# RTI-Dome-eth.net
KiCad netlist of a schematic drawn in EAGLE
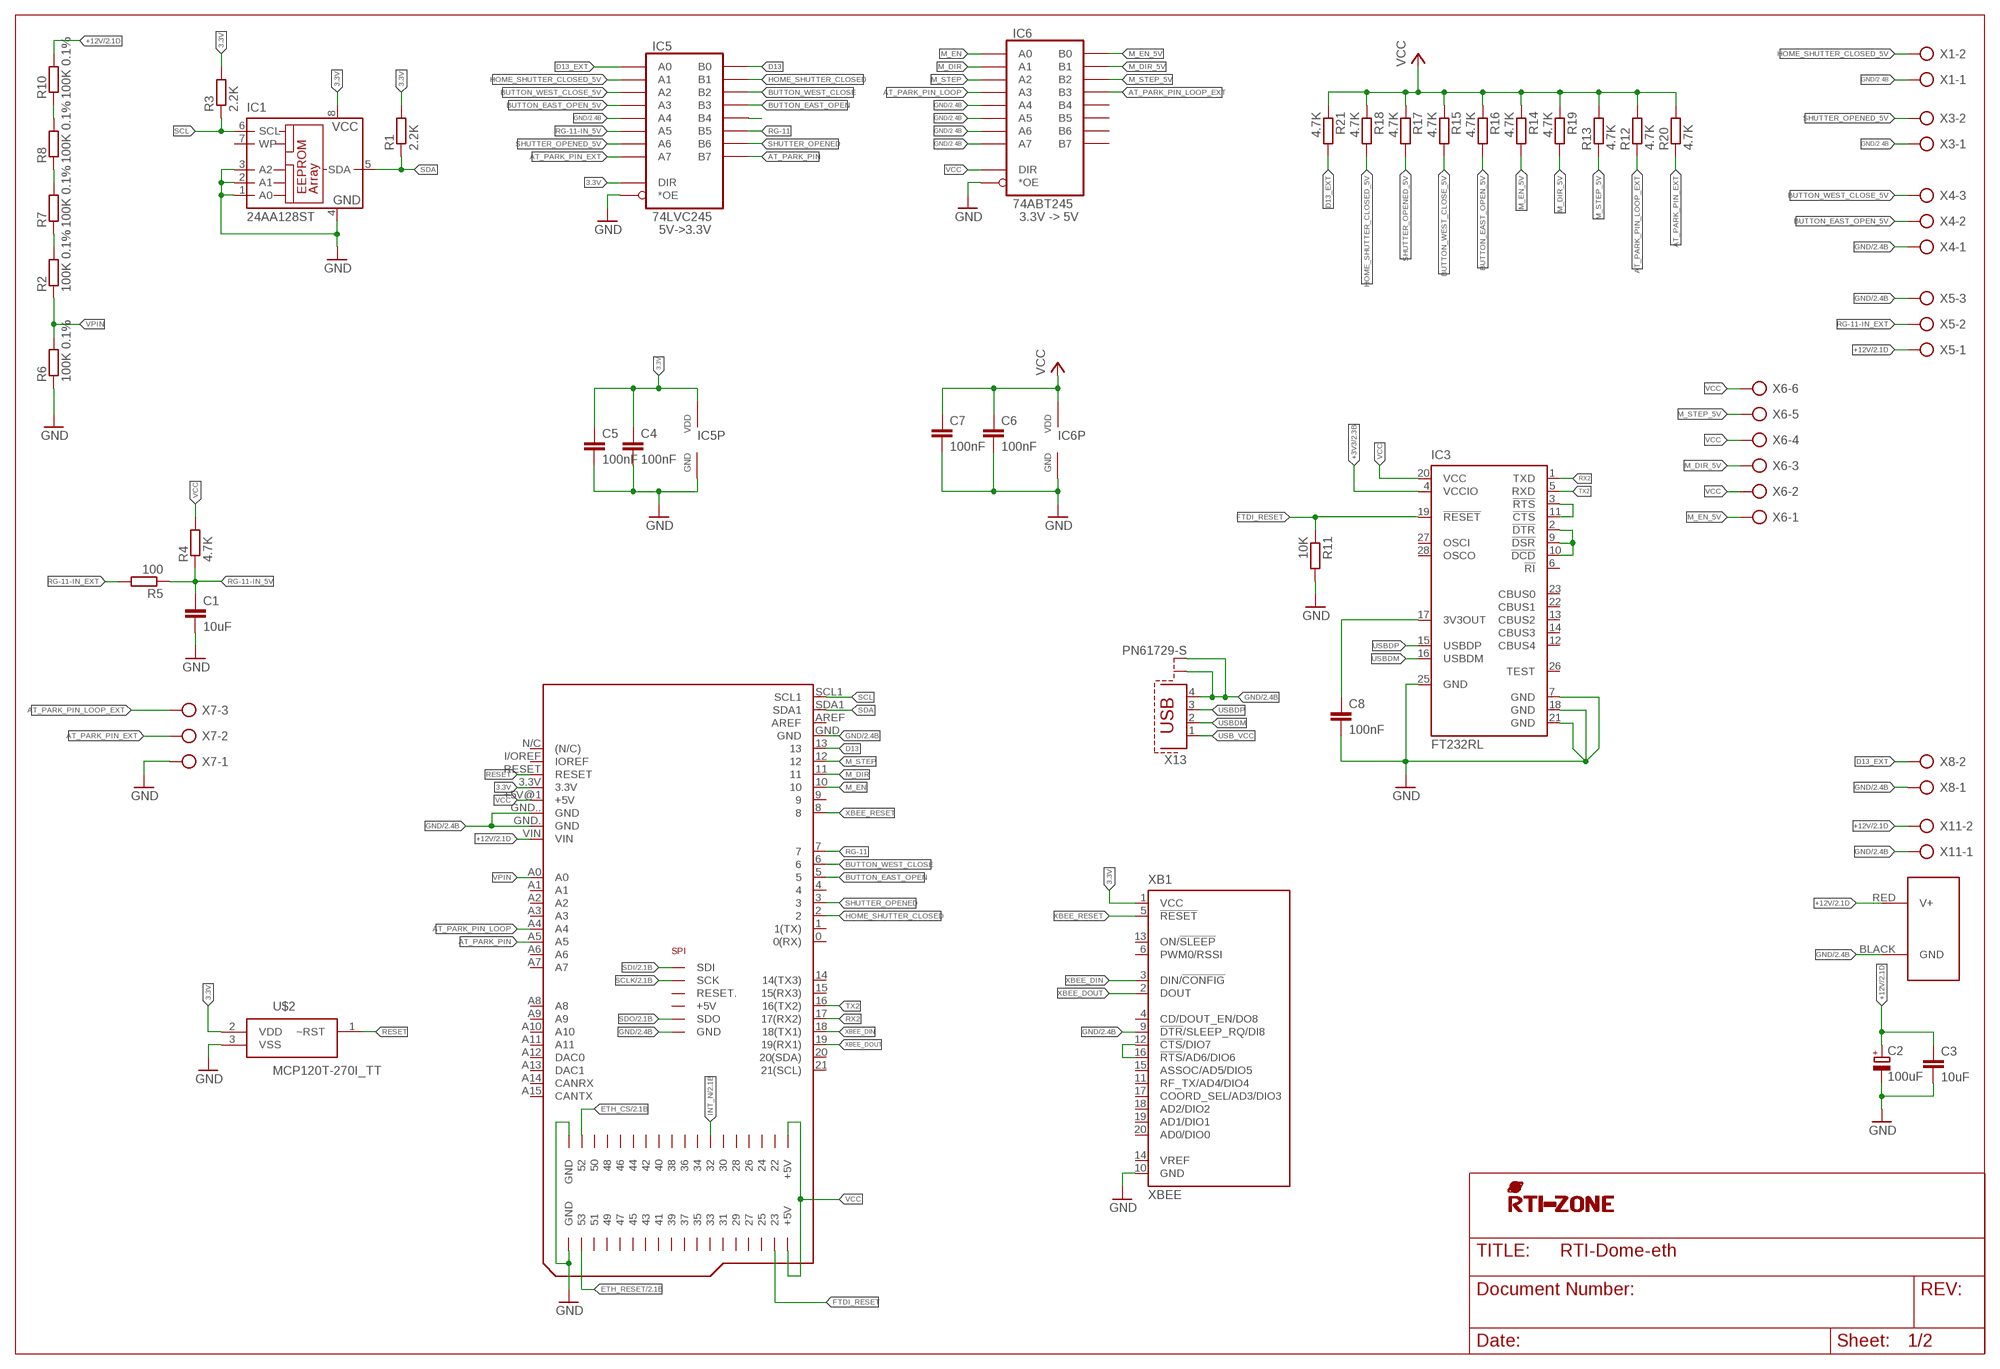
[diagram p0: schematic, sheet 1]
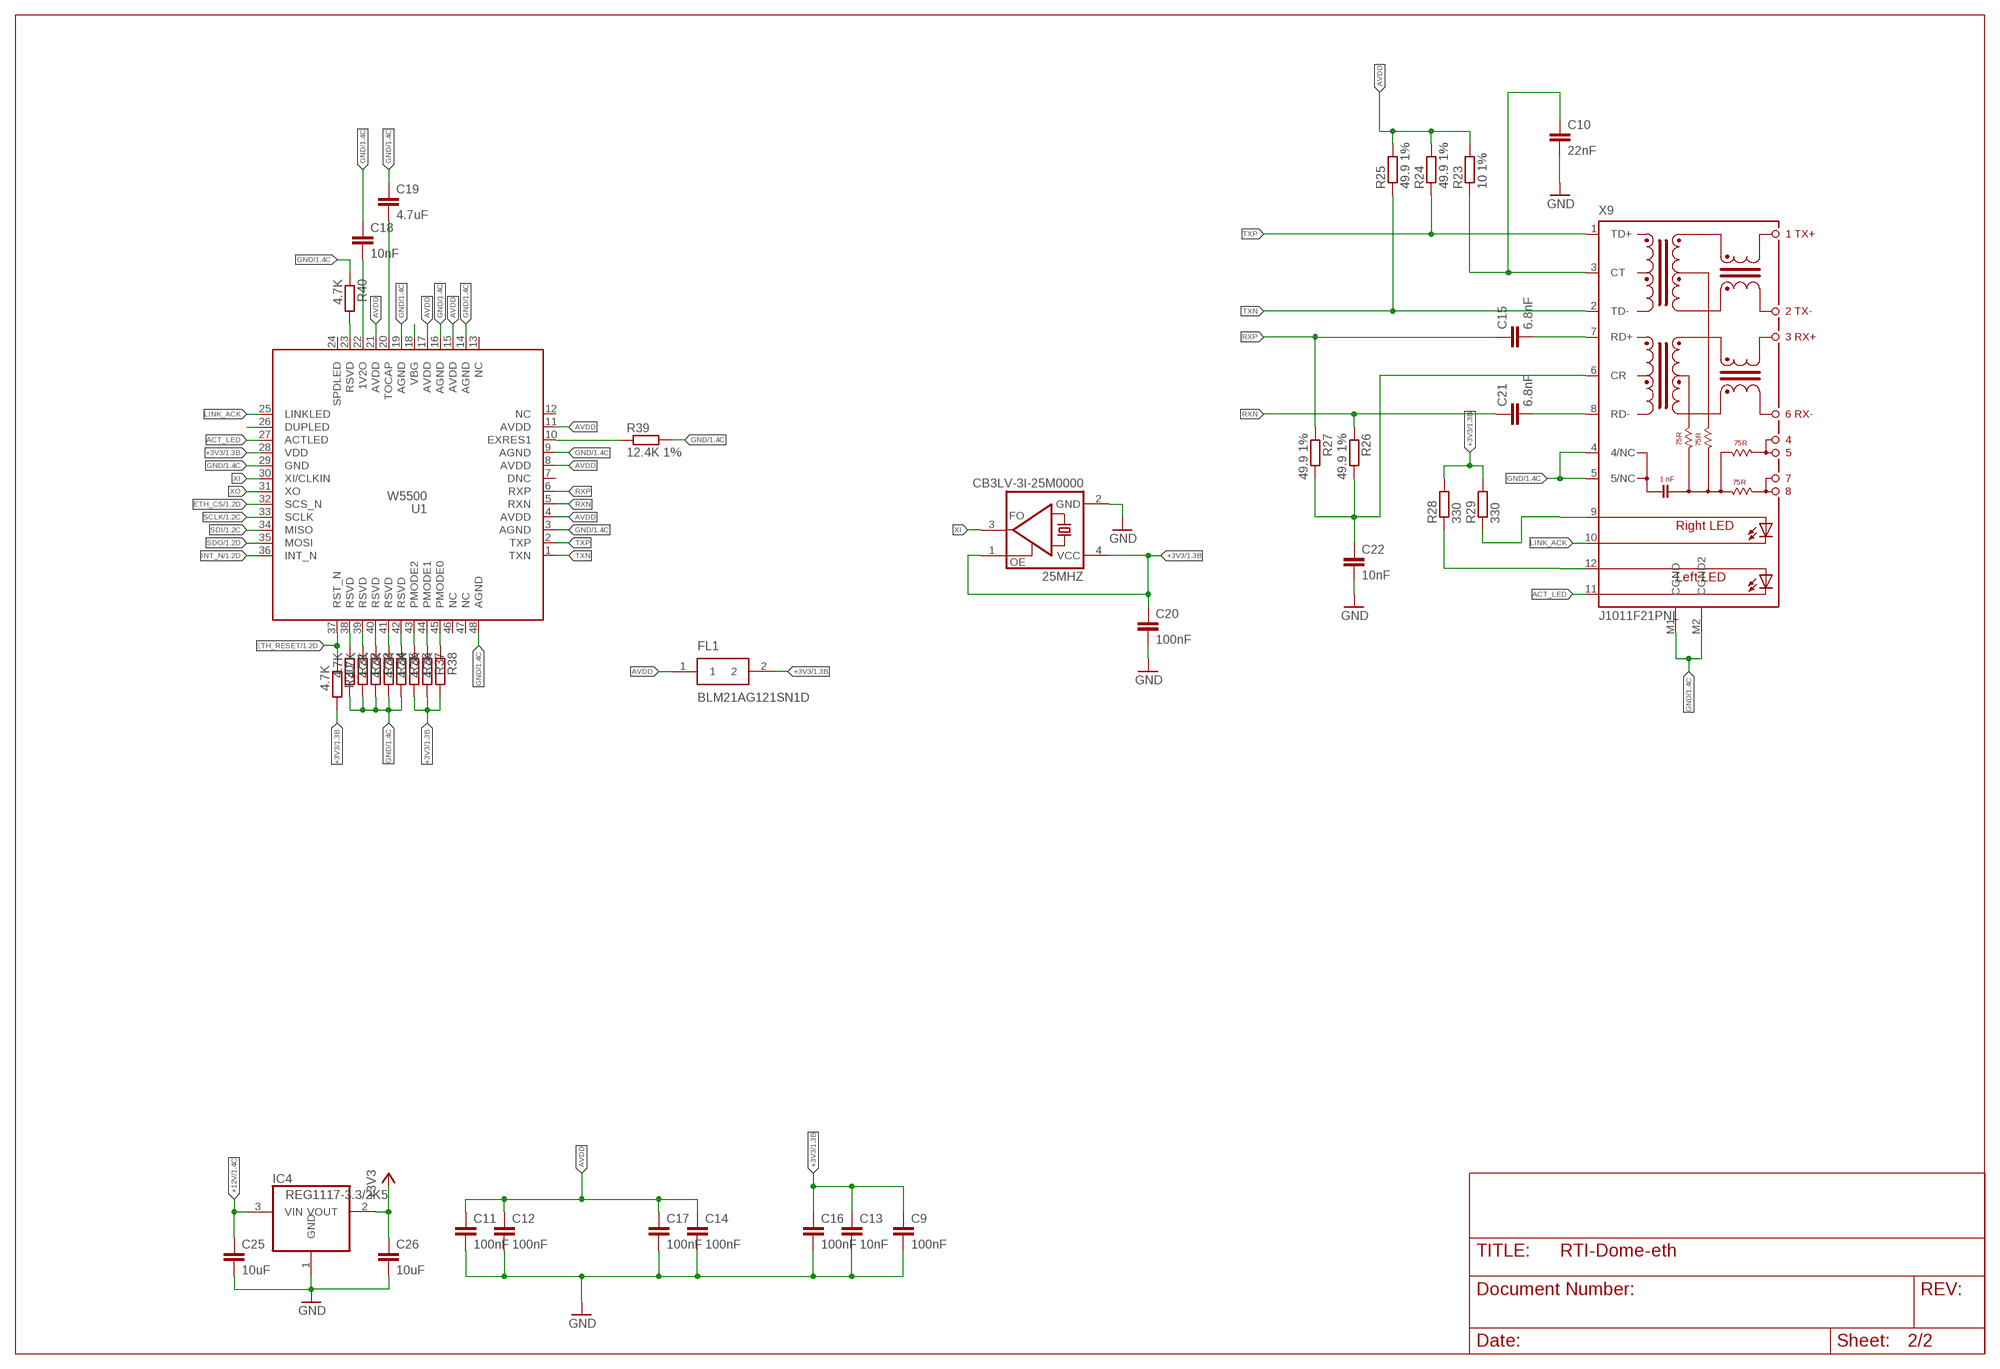
[diagram p1: schematic, sheet 2]

(export (version "E")
  (design (tool "Eeschema 10.0.6"))
  (components
    (comp (ref "C1")
      (value "10uF")
      (footprint "eagle-import:C0805")
      (fields (field (name "MPN") "CC0805KKX5R8BB106"))
      (libsource (lib "eagle-import") (part "C-EU'0805'"))
    )
    (comp (ref "C2")
      (value "100uF")
      (footprint "eagle-import:UD-10X10_NICHICON")
      (fields (field (name "MPN") "MAL215099804E3"))
      (libsource (lib "eagle-import") (part "CPOL-EU"))
    )
    (comp (ref "C3")
      (value "10uF")
      (footprint "eagle-import:C0805")
      (fields (field (name "MPN") "CC0805KKX5R8BB106"))
      (libsource (lib "eagle-import") (part "C-EU'0805'"))
    )
    (comp (ref "C4")
      (value "100nF")
      (footprint "eagle-import:C0805")
      (fields (field (name "MPN") "0805YD104KAT2A"))
      (libsource (lib "eagle-import") (part "C-EU'0805'"))
    )
    (comp (ref "C5")
      (value "100nF")
      (footprint "eagle-import:C0805")
      (fields (field (name "MPN") "0805YD104KAT2A"))
      (libsource (lib "eagle-import") (part "C-EU'0805'"))
    )
    (comp (ref "C6")
      (value "100nF")
      (footprint "eagle-import:C0805")
      (fields (field (name "MPN") "0805YD104KAT2A"))
      (libsource (lib "eagle-import") (part "C-EU'0805'"))
    )
    (comp (ref "C7")
      (value "100nF")
      (footprint "eagle-import:C0805")
      (fields (field (name "MPN") "0805YD104KAT2A"))
      (libsource (lib "eagle-import") (part "C-EU'0805'"))
    )
    (comp (ref "C8")
      (value "100nF")
      (footprint "eagle-import:C0805")
      (fields (field (name "MPN") "0805YD104KAT2A"))
      (libsource (lib "eagle-import") (part "C-EU'0805'"))
    )
    (comp (ref "IC1")
      (value "24AA128ST")
      (footprint "eagle-import:TSSOP8")
      (fields (field (name "MF") "MICROCHIP") (field (name "MPN") "24AA128-I/ST"))
      (libsource (lib "eagle-import") (part "24STAA128"))
    )
    (comp (ref "IC3")
      (value "FT232RL")
      (footprint "eagle-import:SSOP28")
      (fields (field (name "MPN") "FT232RL-REEL"))
      (libsource (lib "eagle-import") (part "FT232RL"))
    )
    (comp (ref "IC5")
      (value "74LVC245")
      (footprint "eagle-import:TSSOP20")
      (fields (field (name "MPN") "74LVC245APW,112"))
      (libsource (lib "eagle-import") (part "74245LVC"))
    )
    (comp (ref "IC6")
      (value "74ABT245")
      (footprint "eagle-import:TSSOP20")
      (fields (field (name "MPN") "74ABT245PW,112"))
      (libsource (lib "eagle-import") (part "74245ABT"))
    )
    (comp (ref "J1")
      (value "POWERPOLE_POWER45A")
      (footprint "eagle-import:POWERPOLE_PAIR_45A")
      (libsource (lib "eagle-import") (part "POWERPOLE_POWER45A"))
    )
    (comp (ref "R1")
      (value "2.2K")
      (footprint "eagle-import:R0805")
      (fields (field (name "MPN") "RT0805FRE071KL"))
      (libsource (lib "eagle-import") (part "R-EU'0805'"))
    )
    (comp (ref "R2")
      (value "100K 0.1%")
      (footprint "eagle-import:R0805")
      (fields (field (name "MPN") "AT0805BRD07100KL"))
      (libsource (lib "eagle-import") (part "R-EU'0805'"))
    )
    (comp (ref "R3")
      (value "2.2K")
      (footprint "eagle-import:R0805")
      (fields (field (name "MPN") "RT0805FRE071KL"))
      (libsource (lib "eagle-import") (part "R-EU'0805'"))
    )
    (comp (ref "R4")
      (value "4.7K")
      (footprint "eagle-import:R0805")
      (fields (field (name "MPN") "RT0805FRE074K7L"))
      (libsource (lib "eagle-import") (part "R-EU'0805'"))
    )
    (comp (ref "R5")
      (value "100")
      (footprint "eagle-import:R0805")
      (fields (field (name "MPN") "RT0805FRD07100RL"))
      (libsource (lib "eagle-import") (part "R-EU'0805'"))
    )
    (comp (ref "R6")
      (value "100K 0.1%")
      (footprint "eagle-import:R0805")
      (fields (field (name "MPN") "AT0805BRD07100KL"))
      (libsource (lib "eagle-import") (part "R-EU'0805'"))
    )
    (comp (ref "R7")
      (value "100K 0.1%")
      (footprint "eagle-import:R0805")
      (fields (field (name "MPN") "AT0805BRD07100KL"))
      (libsource (lib "eagle-import") (part "R-EU'0805'"))
    )
    (comp (ref "R8")
      (value "100K 0.1%")
      (footprint "eagle-import:R0805")
      (fields (field (name "MPN") "AT0805BRD07100KL"))
      (libsource (lib "eagle-import") (part "R-EU'0805'"))
    )
    (comp (ref "R10")
      (value "100K 0.1%")
      (footprint "eagle-import:R0805")
      (fields (field (name "MPN") "AT0805BRD07100KL"))
      (libsource (lib "eagle-import") (part "R-EU'0805'"))
    )
    (comp (ref "R11")
      (value "10K")
      (footprint "eagle-import:R0805")
      (fields (field (name "MPN") "RT0805FRE0710KL"))
      (libsource (lib "eagle-import") (part "R-EU'0805'"))
    )
    (comp (ref "R12")
      (value "4.7K")
      (footprint "eagle-import:R0805")
      (fields (field (name "MPN") "RT0805FRE074K7L"))
      (libsource (lib "eagle-import") (part "R-EU'0805'"))
    )
    (comp (ref "R13")
      (value "4.7K")
      (footprint "eagle-import:R0805")
      (fields (field (name "MPN") "RT0805FRE074K7L"))
      (libsource (lib "eagle-import") (part "R-EU'0805'"))
    )
    (comp (ref "R14")
      (value "4.7K")
      (footprint "eagle-import:R0805")
      (fields (field (name "MPN") "RT0805FRE074K7L"))
      (libsource (lib "eagle-import") (part "R-EU'0805'"))
    )
    (comp (ref "R15")
      (value "4.7K")
      (footprint "eagle-import:R0805")
      (fields (field (name "MPN") "RT0805FRE074K7L"))
      (libsource (lib "eagle-import") (part "R-EU'0805'"))
    )
    (comp (ref "R16")
      (value "4.7K")
      (footprint "eagle-import:R0805")
      (fields (field (name "MPN") "RT0805FRE074K7L"))
      (libsource (lib "eagle-import") (part "R-EU'0805'"))
    )
    (comp (ref "R17")
      (value "4.7K")
      (footprint "eagle-import:R0805")
      (fields (field (name "MPN") "RT0805FRE074K7L"))
      (libsource (lib "eagle-import") (part "R-EU'0805'"))
    )
    (comp (ref "R18")
      (value "4.7K")
      (footprint "eagle-import:R0805")
      (fields (field (name "MPN") "RT0805FRE074K7L"))
      (libsource (lib "eagle-import") (part "R-EU'0805'"))
    )
    (comp (ref "R19")
      (value "4.7K")
      (footprint "eagle-import:R0805")
      (fields (field (name "MPN") "RT0805FRE074K7L"))
      (libsource (lib "eagle-import") (part "R-EU'0805'"))
    )
    (comp (ref "R20")
      (value "4.7K")
      (footprint "eagle-import:R0805")
      (fields (field (name "MPN") "RT0805FRE074K7L"))
      (libsource (lib "eagle-import") (part "R-EU'0805'"))
    )
    (comp (ref "R21")
      (value "4.7K")
      (footprint "eagle-import:R0805")
      (fields (field (name "MPN") "RT0805FRE074K7L"))
      (libsource (lib "eagle-import") (part "R-EU'0805'"))
    )
    (comp (ref "U$1")
      (value "ARDUINO_DUE_SHIELD_FULL")
      (footprint "eagle-import:ARDUINO_DUE_SHIELD_FULL")
      (libsource (lib "eagle-import") (part "ARDUINO_DUE_SHIELD_FULL"))
    )
    (comp (ref "U$2")
      (value "MCP120T-270I_TT")
      (footprint "eagle-import:SOT95P237X112-3N")
      (fields
        (field (name "MANUFACTURER_PART_NUMBER") "MCP120T-270I/TT")
        (field (name "MOUSER_PART_NUMBER") "579-MCP120T-270I/TT")
      )
      (libsource (lib "eagle-import") (part "MCP120T-270I_TT"))
    )
    (comp (ref "U$4")
      (value "RTI-LOGO_BIG")
      (footprint "eagle-import:LOGO_BIG")
      (libsource (lib "eagle-import") (part "RTI-LOGO_BIG"))
    )
    (comp (ref "X1")
      (value "AK500/2")
      (footprint "eagle-import:AK500_2")
      (fields (field (name "MPN") "691101710002"))
      (libsource (lib "eagle-import") (part "AK500/2"))
    )
    (comp (ref "X3")
      (value "AK500/2")
      (footprint "eagle-import:AK500_2")
      (fields (field (name "MPN") "691101710002"))
      (libsource (lib "eagle-import") (part "AK500/2"))
    )
    (comp (ref "X4")
      (value "AK500/3")
      (footprint "eagle-import:AK500_3")
      (fields (field (name "MPN") "691101710003"))
      (libsource (lib "eagle-import") (part "AK500/3"))
    )
    (comp (ref "X5")
      (value "AK500/3")
      (footprint "eagle-import:AK500_3")
      (fields (field (name "MPN") "691101710003"))
      (libsource (lib "eagle-import") (part "AK500/3"))
    )
    (comp (ref "X6")
      (value "AK500/6")
      (footprint "eagle-import:AK500_6")
      (fields (field (name "MPN") "30.706"))
      (libsource (lib "eagle-import") (part "AK500/6"))
    )
    (comp (ref "X7")
      (value "AK500/3")
      (footprint "eagle-import:AK500_3")
      (fields (field (name "MPN") "691101710003"))
      (libsource (lib "eagle-import") (part "AK500/3"))
    )
    (comp (ref "X8")
      (value "AK500/2")
      (footprint "eagle-import:AK500_2")
      (fields (field (name "MPN") "691101710002"))
      (libsource (lib "eagle-import") (part "AK500/2"))
    )
    (comp (ref "X11")
      (value "AK500/2")
      (footprint "eagle-import:AK500_2")
      (fields (field (name "MPN") "691101710002"))
      (libsource (lib "eagle-import") (part "AK500/2"))
    )
    (comp (ref "X13")
      (value "PN61729-S")
      (footprint "eagle-import:PN61729-S")
      (fields (field (name "MPN") "SS-52300-001"))
      (libsource (lib "eagle-import") (part "PN61729-S"))
    )
    (comp (ref "XB1")
      (value "XBEE")
      (footprint "eagle-import:XBEE")
      (fields (field (name "MPN") "XBP24-Z7UIT-004"))
      (libsource (lib "eagle-import") (part "XBEE"))
    )
    (comp (ref "25MHZ")
      (value "CB3LV-3I-25M0000")
      (footprint "eagle-import:SMD-7050_4P")
      (libsource (lib "eagle-import") (part "CB3LV-OSCILATOR"))
    )
    (comp (ref "C9")
      (value "100nF")
      (footprint "eagle-import:C0805")
      (fields (field (name "MPN") "0805YD104KAT2A"))
      (libsource (lib "eagle-import") (part "C-EU'0805'"))
    )
    (comp (ref "C10")
      (value "22nF")
      (footprint "eagle-import:C0805")
      (fields (field (name "MPN") "CC0805JRX7R8BB223"))
      (libsource (lib "eagle-import") (part "C-EU'0805'"))
    )
    (comp (ref "C11")
      (value "100nF")
      (footprint "eagle-import:C0805")
      (fields (field (name "MPN") "0805YD104KAT2A"))
      (libsource (lib "eagle-import") (part "C-EU'0805'"))
    )
    (comp (ref "C12")
      (value "100nF")
      (footprint "eagle-import:C0805")
      (fields (field (name "MPN") "0805YD104KAT2A"))
      (libsource (lib "eagle-import") (part "C-EU'0805'"))
    )
    (comp (ref "C13")
      (value "10nF")
      (footprint "eagle-import:C0805")
      (fields (field (name "MPN") " CC0805KRX7R9BB103"))
      (libsource (lib "eagle-import") (part "C-EU'0805'"))
    )
    (comp (ref "C14")
      (value "100nF")
      (footprint "eagle-import:C0805")
      (fields (field (name "MPN") "0805YD104KAT2A"))
      (libsource (lib "eagle-import") (part "C-EU'0805'"))
    )
    (comp (ref "C15")
      (value "6.8nF")
      (footprint "eagle-import:C0805")
      (fields (field (name "MPN") "C0805C682F4HACTU"))
      (libsource (lib "eagle-import") (part "C-EU'0805'"))
    )
    (comp (ref "C16")
      (value "100nF")
      (footprint "eagle-import:C0805")
      (fields (field (name "MPN") "0805YD104KAT2A"))
      (libsource (lib "eagle-import") (part "C-EU'0805'"))
    )
    (comp (ref "C17")
      (value "100nF")
      (footprint "eagle-import:C0805")
      (fields (field (name "MPN") "0805YD104KAT2A"))
      (libsource (lib "eagle-import") (part "C-EU'0805'"))
    )
    (comp (ref "C18")
      (value "10nF")
      (footprint "eagle-import:C0805")
      (fields (field (name "MPN") " CC0805KRX7R9BB103"))
      (libsource (lib "eagle-import") (part "C-EU'0805'"))
    )
    (comp (ref "C19")
      (value "4.7uF")
      (footprint "eagle-import:C0805")
      (fields (field (name "MPN") "C0805C475J3RACTU"))
      (libsource (lib "eagle-import") (part "C-EU'0805'"))
    )
    (comp (ref "C20")
      (value "100nF")
      (footprint "eagle-import:C0805")
      (fields (field (name "MPN") "0805YD104KAT2A"))
      (libsource (lib "eagle-import") (part "C-EU'0805'"))
    )
    (comp (ref "C21")
      (value "6.8nF")
      (footprint "eagle-import:C0805")
      (fields (field (name "MPN") "C0805C682F4HACTU"))
      (libsource (lib "eagle-import") (part "C-EU'0805'"))
    )
    (comp (ref "C22")
      (value "10nF")
      (footprint "eagle-import:C0805")
      (fields (field (name "MPN") " CC0805KRX7R9BB103"))
      (libsource (lib "eagle-import") (part "C-EU'0805'"))
    )
    (comp (ref "C25")
      (value "10uF")
      (footprint "eagle-import:C0805")
      (fields (field (name "MPN") "CC0805KKX5R8BB106"))
      (libsource (lib "eagle-import") (part "C-EU'0805'"))
    )
    (comp (ref "C26")
      (value "10uF")
      (footprint "eagle-import:C0805")
      (fields (field (name "MPN") "CC0805KKX5R8BB106"))
      (libsource (lib "eagle-import") (part "C-EU'0805'"))
    )
    (comp (ref "FL1")
      (value "BLM21AG121SN1D")
      (footprint "eagle-import:L0805")
      (libsource (lib "eagle-import") (part "BLM21AG121SN1D"))
    )
    (comp (ref "IC4")
      (value "REG1117-3.3/2K5")
      (footprint "eagle-import:SOT223")
      (fields (field (name "MPN") "REG1117") (field (name "MPN_1") "REG1117-3.3/2K5"))
      (libsource (lib "eagle-import") (part "REG1117"))
    )
    (comp (ref "R23")
      (value "10 1%")
      (footprint "eagle-import:R0805")
      (fields (field (name "MPN") "RT0805FRE1310RL"))
      (libsource (lib "eagle-import") (part "R-EU'0805'"))
    )
    (comp (ref "R24")
      (value "49.9 1%")
      (footprint "eagle-import:R0805")
      (fields (field (name "MPN") "RC0805FR-0749R9L"))
      (libsource (lib "eagle-import") (part "R-EU'0805'"))
    )
    (comp (ref "R25")
      (value "49.9 1%")
      (footprint "eagle-import:R0805")
      (fields (field (name "MPN") "RC0805FR-0749R9L"))
      (libsource (lib "eagle-import") (part "R-EU'0805'"))
    )
    (comp (ref "R26")
      (value "49.9 1%")
      (footprint "eagle-import:R0805")
      (fields (field (name "MPN") "RC0805FR-0749R9L"))
      (libsource (lib "eagle-import") (part "R-EU'0805'"))
    )
    (comp (ref "R27")
      (value "49.9 1%")
      (footprint "eagle-import:R0805")
      (fields (field (name "MPN") "RC0805FR-0749R9L"))
      (libsource (lib "eagle-import") (part "R-EU'0805'"))
    )
    (comp (ref "R28")
      (value "330")
      (footprint "eagle-import:R0805")
      (fields (field (name "MPN") " RC0805JR-07330RL"))
      (libsource (lib "eagle-import") (part "R-EU'0805'"))
    )
    (comp (ref "R29")
      (value "330")
      (footprint "eagle-import:R0805")
      (fields (field (name "MPN") " RC0805JR-07330RL"))
      (libsource (lib "eagle-import") (part "R-EU'0805'"))
    )
    (comp (ref "R30")
      (value "4.7K")
      (footprint "eagle-import:R0805")
      (fields (field (name "MPN") "RT0805FRE074K7L"))
      (libsource (lib "eagle-import") (part "R-EU'0805'"))
    )
    (comp (ref "R31")
      (value "4.7K")
      (footprint "eagle-import:R0805")
      (fields (field (name "MPN") "RT0805FRE074K7L"))
      (libsource (lib "eagle-import") (part "R-EU'0805'"))
    )
    (comp (ref "R32")
      (value "4.7K")
      (footprint "eagle-import:R0805")
      (fields (field (name "MPN") "RT0805FRE074K7L"))
      (libsource (lib "eagle-import") (part "R-EU'0805'"))
    )
    (comp (ref "R33")
      (value "4.7K")
      (footprint "eagle-import:R0805")
      (fields (field (name "MPN") "RT0805FRE074K7L"))
      (libsource (lib "eagle-import") (part "R-EU'0805'"))
    )
    (comp (ref "R34")
      (value "4.7K")
      (footprint "eagle-import:R0805")
      (fields (field (name "MPN") "RT0805FRE074K7L"))
      (libsource (lib "eagle-import") (part "R-EU'0805'"))
    )
    (comp (ref "R35")
      (value "4.7K")
      (footprint "eagle-import:R0805")
      (fields (field (name "MPN") "RT0805FRE074K7L"))
      (libsource (lib "eagle-import") (part "R-EU'0805'"))
    )
    (comp (ref "R36")
      (value "4.7K")
      (footprint "eagle-import:R0805")
      (fields (field (name "MPN") "RT0805FRE074K7L"))
      (libsource (lib "eagle-import") (part "R-EU'0805'"))
    )
    (comp (ref "R37")
      (value "4.7K")
      (footprint "eagle-import:R0805")
      (fields (field (name "MPN") "RT0805FRE074K7L"))
      (libsource (lib "eagle-import") (part "R-EU'0805'"))
    )
    (comp (ref "R38")
      (value "4.7K")
      (footprint "eagle-import:R0805")
      (fields (field (name "MPN") "RT0805FRE074K7L"))
      (libsource (lib "eagle-import") (part "R-EU'0805'"))
    )
    (comp (ref "R39")
      (value "12.4K 1%")
      (footprint "eagle-import:R0805")
      (fields (field (name "MPN") "RC0805FR-0712K4L"))
      (libsource (lib "eagle-import") (part "R-EU'0805'"))
    )
    (comp (ref "R40")
      (value "4.7K")
      (footprint "eagle-import:R0805")
      (fields (field (name "MPN") "RT0805FRE074K7L"))
      (libsource (lib "eagle-import") (part "R-EU'0805'"))
    )
    (comp (ref "U1")
      (value "W5500")
      (footprint "eagle-import:LQFP48")
      (libsource (lib "eagle-import") (part "W5500"))
    )
    (comp (ref "X9")
      (value "J1011F21PNL")
      (footprint "eagle-import:J1011F21PNL")
      (fields (field (name "MPN") "J1011F21PNL"))
      (libsource (lib "eagle-import") (part "J1011F21PNL"))
    )
  )
  (nets
    (net (code "1") (name "+3V3") (class "Default")
      (node (ref "25MHZ") (pin "1") (pinfunction "OE_1") (pintype "input"))
      (node (ref "25MHZ") (pin "4") (pinfunction "VDD_4") (pintype "power_in"))
      (node (ref "C13") (pin "1") (pinfunction "1_1") (pintype "passive"))
      (node (ref "C16") (pin "1") (pinfunction "1_1") (pintype "passive"))
      (node (ref "C20") (pin "1") (pinfunction "1_1") (pintype "passive"))
      (node (ref "C26") (pin "1") (pinfunction "1_1") (pintype "passive"))
      (node (ref "C9") (pin "1") (pinfunction "1_1") (pintype "passive"))
      (node (ref "FL1") (pin "2") (pinfunction "2_2") (pintype "bidirectional"))
      (node (ref "IC3") (pin "4") (pinfunction "VCCIO_4") (pintype "power_in"))
      (node (ref "IC4") (pin "2") (pinfunction "VOUT_2") (pintype "output"))
      (node (ref "R28") (pin "2") (pinfunction "2_2") (pintype "passive"))
      (node (ref "R29") (pin "2") (pinfunction "2_2") (pintype "passive"))
      (node (ref "R30") (pin "2") (pinfunction "2_2") (pintype "passive"))
      (node (ref "R36") (pin "2") (pinfunction "2_2") (pintype "passive"))
      (node (ref "R37") (pin "2") (pinfunction "2_2") (pintype "passive"))
      (node (ref "R38") (pin "2") (pinfunction "2_2") (pintype "passive"))
      (node (ref "U1") (pin "28") (pinfunction "VDD_28") (pintype "passive"))
    )
    (net (code "2") (name "+5V") (class "Default")
      (node (ref "U$1") (pin "+5V@2") (pinfunction "+5V_+5V@2") (pintype "power_in"))
    )
    (net (code "3") (name "+12V") (class "Default")
      (node (ref "C2") (pin "+") (pinfunction "+_+") (pintype "passive"))
      (node (ref "C25") (pin "1") (pinfunction "1_1") (pintype "passive"))
      (node (ref "C3") (pin "1") (pinfunction "1_1") (pintype "passive"))
      (node (ref "IC4") (pin "3") (pinfunction "VIN_3") (pintype "input"))
      (node (ref "J1") (pin "RED") (pinfunction "V+_RED") (pintype "power_in"))
      (node (ref "R10") (pin "2") (pinfunction "2_2") (pintype "passive"))
      (node (ref "U$1") (pin "VIN") (pinfunction "VIN_VIN") (pintype "power_in"))
      (node (ref "X11") (pin "2") (pinfunction "KL_2") (pintype "passive"))
      (node (ref "X5") (pin "1") (pinfunction "KL_1") (pintype "passive"))
    )
    (net (code "4") (name "3.3V") (class "Default")
      (node (ref "C4") (pin "1") (pinfunction "1_1") (pintype "passive"))
      (node (ref "C5") (pin "1") (pinfunction "1_1") (pintype "passive"))
      (node (ref "IC1") (pin "8") (pinfunction "VCC_8") (pintype "power_in"))
      (node (ref "IC5") (pin "P$1") (pinfunction "DIR_P$1") (pintype "input"))
      (node (ref "IC5") (pin "P$20") (pinfunction "VDD_P$20") (pintype "power_in"))
      (node (ref "R1") (pin "2") (pinfunction "2_2") (pintype "passive"))
      (node (ref "R3") (pin "2") (pinfunction "2_2") (pintype "passive"))
      (node (ref "U$1") (pin "3.3V") (pinfunction "3.3V_3.3V") (pintype "power_in"))
      (node (ref "U$2") (pin "2") (pinfunction "VDD_2") (pintype "bidirectional"))
      (node (ref "XB1") (pin "1") (pinfunction "VCC_1") (pintype "power_in"))
    )
    (net (code "5") (name "ACT_LED") (class "Default")
      (node (ref "U1") (pin "27") (pinfunction "ACTLED_27") (pintype "passive"))
      (node (ref "X9") (pin "11") (pinfunction "C-L_11") (pintype "passive"))
    )
    (net (code "6") (name "AT_PARK_PIN") (class "Default")
      (node (ref "IC5") (pin "P$11") (pinfunction "B7_P$11") (pintype "bidirectional"))
      (node (ref "U$1") (pin "A5") (pinfunction "A5_A5") (pintype "bidirectional"))
    )
    (net (code "7") (name "AT_PARK_PIN_EXT") (class "Default")
      (node (ref "IC5") (pin "P$9") (pinfunction "A7_P$9") (pintype "bidirectional"))
      (node (ref "R20") (pin "1") (pinfunction "1_1") (pintype "passive"))
      (node (ref "X7") (pin "2") (pinfunction "KL_2") (pintype "passive"))
    )
    (net (code "8") (name "AT_PARK_PIN_LOOP") (class "Default")
      (node (ref "IC6") (pin "P$5") (pinfunction "A3_P$5") (pintype "bidirectional"))
      (node (ref "U$1") (pin "A4") (pinfunction "A4_A4") (pintype "bidirectional"))
    )
    (net (code "9") (name "AT_PARK_PIN_LOOP_EXT") (class "Default")
      (node (ref "IC6") (pin "P$15") (pinfunction "B3_P$15") (pintype "bidirectional"))
      (node (ref "R12") (pin "1") (pinfunction "1_1") (pintype "passive"))
      (node (ref "X7") (pin "3") (pinfunction "KL_3") (pintype "passive"))
    )
    (net (code "10") (name "AVDD") (class "Default")
      (node (ref "C11") (pin "1") (pinfunction "1_1") (pintype "passive"))
      (node (ref "C12") (pin "1") (pinfunction "1_1") (pintype "passive"))
      (node (ref "C14") (pin "1") (pinfunction "1_1") (pintype "passive"))
      (node (ref "C17") (pin "1") (pinfunction "1_1") (pintype "passive"))
      (node (ref "FL1") (pin "1") (pinfunction "1_1") (pintype "bidirectional"))
      (node (ref "R23") (pin "2") (pinfunction "2_2") (pintype "passive"))
      (node (ref "R24") (pin "2") (pinfunction "2_2") (pintype "passive"))
      (node (ref "R25") (pin "2") (pinfunction "2_2") (pintype "passive"))
      (node (ref "U1") (pin "11") (pinfunction "AVDD_11") (pintype "passive"))
      (node (ref "U1") (pin "15") (pinfunction "AVDD_15") (pintype "passive"))
      (node (ref "U1") (pin "17") (pinfunction "AVDD_17") (pintype "passive"))
      (node (ref "U1") (pin "21") (pinfunction "AVDD_21") (pintype "passive"))
      (node (ref "U1") (pin "4") (pinfunction "AVDD_4") (pintype "passive"))
      (node (ref "U1") (pin "8") (pinfunction "AVDD_8") (pintype "passive"))
    )
    (net (code "11") (name "BUTTON_EAST_OPEN") (class "Default")
      (node (ref "IC5") (pin "P$15") (pinfunction "B3_P$15") (pintype "bidirectional"))
      (node (ref "U$1") (pin "5") (pinfunction "5_5") (pintype "bidirectional"))
    )
    (net (code "12") (name "BUTTON_EAST_OPEN_5V") (class "Default")
      (node (ref "IC5") (pin "P$5") (pinfunction "A3_P$5") (pintype "bidirectional"))
      (node (ref "R16") (pin "2") (pinfunction "2_2") (pintype "passive"))
      (node (ref "X4") (pin "2") (pinfunction "KL_2") (pintype "passive"))
    )
    (net (code "13") (name "BUTTON_WEST_CLOSE") (class "Default")
      (node (ref "IC5") (pin "P$16") (pinfunction "B2_P$16") (pintype "bidirectional"))
      (node (ref "U$1") (pin "6") (pinfunction "6_6") (pintype "bidirectional"))
    )
    (net (code "14") (name "BUTTON_WEST_CLOSE_5V") (class "Default")
      (node (ref "IC5") (pin "P$4") (pinfunction "A2_P$4") (pintype "bidirectional"))
      (node (ref "R15") (pin "2") (pinfunction "2_2") (pintype "passive"))
      (node (ref "X4") (pin "3") (pinfunction "KL_3") (pintype "passive"))
    )
    (net (code "15") (name "D13") (class "Default")
      (node (ref "IC5") (pin "P$18") (pinfunction "B0_P$18") (pintype "bidirectional"))
      (node (ref "U$1") (pin "13") (pinfunction "13_13") (pintype "bidirectional"))
    )
    (net (code "16") (name "D13_EXT") (class "Default")
      (node (ref "IC5") (pin "P$2") (pinfunction "A0_P$2") (pintype "bidirectional"))
      (node (ref "R21") (pin "2") (pinfunction "2_2") (pintype "passive"))
      (node (ref "X8") (pin "2") (pinfunction "KL_2") (pintype "passive"))
    )
    (net (code "17") (name "ETH_CS") (class "Default")
      (node (ref "U$1") (pin "52") (pinfunction "52_52") (pintype "bidirectional"))
      (node (ref "U1") (pin "32") (pinfunction "SCS_N_32") (pintype "passive"))
    )
    (net (code "18") (name "ETH_RESET") (class "Default")
      (node (ref "R30") (pin "1") (pinfunction "1_1") (pintype "passive"))
      (node (ref "U$1") (pin "53") (pinfunction "53_53") (pintype "bidirectional"))
      (node (ref "U1") (pin "37") (pinfunction "RST_N_37") (pintype "passive"))
    )
    (net (code "19") (name "FTDI_RESET") (class "Default")
      (node (ref "IC3") (pin "19") (pinfunction "~{RESET}_19") (pintype "input"))
      (node (ref "R11") (pin "1") (pinfunction "1_1") (pintype "passive"))
      (node (ref "U$1") (pin "23") (pinfunction "23_23") (pintype "bidirectional"))
    )
    (net (code "20") (name "GND") (class "Default")
      (node (ref "25MHZ") (pin "2") (pinfunction "GND_2") (pintype "power_in"))
      (node (ref "C1") (pin "2") (pinfunction "2_2") (pintype "passive"))
      (node (ref "C10") (pin "2") (pinfunction "2_2") (pintype "passive"))
      (node (ref "C11") (pin "2") (pinfunction "2_2") (pintype "passive"))
      (node (ref "C12") (pin "2") (pinfunction "2_2") (pintype "passive"))
      (node (ref "C13") (pin "2") (pinfunction "2_2") (pintype "passive"))
      (node (ref "C14") (pin "2") (pinfunction "2_2") (pintype "passive"))
      (node (ref "C16") (pin "2") (pinfunction "2_2") (pintype "passive"))
      (node (ref "C17") (pin "2") (pinfunction "2_2") (pintype "passive"))
      (node (ref "C18") (pin "1") (pinfunction "1_1") (pintype "passive"))
      (node (ref "C19") (pin "1") (pinfunction "1_1") (pintype "passive"))
      (node (ref "C2") (pin "-") (pinfunction "-_-") (pintype "passive"))
      (node (ref "C20") (pin "2") (pinfunction "2_2") (pintype "passive"))
      (node (ref "C22") (pin "2") (pinfunction "2_2") (pintype "passive"))
      (node (ref "C25") (pin "2") (pinfunction "2_2") (pintype "passive"))
      (node (ref "C26") (pin "2") (pinfunction "2_2") (pintype "passive"))
      (node (ref "C3") (pin "2") (pinfunction "2_2") (pintype "passive"))
      (node (ref "C4") (pin "2") (pinfunction "2_2") (pintype "passive"))
      (node (ref "C5") (pin "2") (pinfunction "2_2") (pintype "passive"))
      (node (ref "C6") (pin "2") (pinfunction "2_2") (pintype "passive"))
      (node (ref "C7") (pin "2") (pinfunction "2_2") (pintype "passive"))
      (node (ref "C8") (pin "2") (pinfunction "2_2") (pintype "passive"))
      (node (ref "C9") (pin "2") (pinfunction "2_2") (pintype "passive"))
      (node (ref "IC1") (pin "1") (pinfunction "A0_1") (pintype "input"))
      (node (ref "IC1") (pin "2") (pinfunction "A1_2") (pintype "input"))
      (node (ref "IC1") (pin "3") (pinfunction "A2_3") (pintype "input"))
      (node (ref "IC1") (pin "4") (pinfunction "GND_4") (pintype "power_in"))
      (node (ref "IC3") (pin "18") (pinfunction "GND_18") (pintype "power_in"))
      (node (ref "IC3") (pin "21") (pinfunction "GND_21") (pintype "power_in"))
      (node (ref "IC3") (pin "25") (pinfunction "GND_25") (pintype "power_in"))
      (node (ref "IC3") (pin "7") (pinfunction "GND_7") (pintype "power_in"))
      (node (ref "IC4") (pin "1") (pinfunction "GND_1") (pintype "power_in"))
      (node (ref "IC5") (pin "P$10") (pinfunction "GND_P$10") (pintype "power_in"))
      (node (ref "IC5") (pin "P$19") (pinfunction "*OE_P$19") (pintype "input"))
      (node (ref "IC5") (pin "P$6") (pinfunction "A4_P$6") (pintype "bidirectional"))
      (node (ref "IC6") (pin "P$10") (pinfunction "GND_P$10") (pintype "power_in"))
      (node (ref "IC6") (pin "P$19") (pinfunction "*OE_P$19") (pintype "input"))
      (node (ref "IC6") (pin "P$6") (pinfunction "A4_P$6") (pintype "bidirectional"))
      (node (ref "IC6") (pin "P$7") (pinfunction "A5_P$7") (pintype "bidirectional"))
      (node (ref "IC6") (pin "P$8") (pinfunction "A6_P$8") (pintype "bidirectional"))
      (node (ref "IC6") (pin "P$9") (pinfunction "A7_P$9") (pintype "bidirectional"))
      (node (ref "J1") (pin "BLACK") (pinfunction "GND_BLACK") (pintype "power_in"))
      (node (ref "R11") (pin "2") (pinfunction "2_2") (pintype "passive"))
      (node (ref "R31") (pin "2") (pinfunction "2_2") (pintype "passive"))
      (node (ref "R32") (pin "2") (pinfunction "2_2") (pintype "passive"))
      (node (ref "R33") (pin "2") (pinfunction "2_2") (pintype "passive"))
      (node (ref "R34") (pin "2") (pinfunction "2_2") (pintype "passive"))
      (node (ref "R35") (pin "2") (pinfunction "2_2") (pintype "passive"))
      (node (ref "R39") (pin "2") (pinfunction "2_2") (pintype "passive"))
      (node (ref "R40") (pin "1") (pinfunction "1_1") (pintype "passive"))
      (node (ref "R6") (pin "1") (pinfunction "1_1") (pintype "passive"))
      (node (ref "U$1") (pin "GND") (pinfunction "GND_GND") (pintype "power_in"))
      (node (ref "U$1") (pin "GND.") (pinfunction "GND_GND.") (pintype "power_in"))
      (node (ref "U$1") (pin "GND..") (pinfunction "GND_GND..") (pintype "power_in"))
      (node (ref "U$1") (pin "GND...") (pinfunction "GND_GND...") (pintype "power_in"))
      (node (ref "U$1") (pin "GND....") (pinfunction "GND_GND....") (pintype "power_in"))
      (node (ref "U$1") (pin "GND__") (pinfunction "GND_GND__") (pintype "power_in"))
      (node (ref "U$2") (pin "3") (pinfunction "VSS_3") (pintype "bidirectional"))
      (node (ref "U1") (pin "14") (pinfunction "AGND_14") (pintype "passive"))
      (node (ref "U1") (pin "16") (pinfunction "AGND_16") (pintype "passive"))
      (node (ref "U1") (pin "19") (pinfunction "AGND_19") (pintype "passive"))
      (node (ref "U1") (pin "29") (pinfunction "GND_29") (pintype "passive"))
      (node (ref "U1") (pin "3") (pinfunction "AGND_3") (pintype "passive"))
      (node (ref "U1") (pin "48") (pinfunction "AGND_48") (pintype "passive"))
      (node (ref "U1") (pin "9") (pinfunction "AGND_9") (pintype "passive"))
      (node (ref "X1") (pin "1") (pinfunction "KL_1") (pintype "passive"))
      (node (ref "X11") (pin "1") (pinfunction "KL_1") (pintype "passive"))
      (node (ref "X13") (pin "4") (pinfunction "4_4") (pintype "passive"))
      (node (ref "X13") (pin "S1") (pinfunction "S1_S1") (pintype "passive"))
      (node (ref "X13") (pin "S2") (pinfunction "S2_S2") (pintype "passive"))
      (node (ref "X3") (pin "1") (pinfunction "KL_1") (pintype "passive"))
      (node (ref "X4") (pin "1") (pinfunction "KL_1") (pintype "passive"))
      (node (ref "X5") (pin "3") (pinfunction "KL_3") (pintype "passive"))
      (node (ref "X7") (pin "1") (pinfunction "KL_1") (pintype "passive"))
      (node (ref "X8") (pin "1") (pinfunction "KL_1") (pintype "passive"))
      (node (ref "X9") (pin "4") (pinfunction "4/NC_4") (pintype "input"))
      (node (ref "X9") (pin "5") (pinfunction "5/NC_5") (pintype "input"))
      (node (ref "X9") (pin "M1") (pinfunction "CGND_M1") (pintype "bidirectional"))
      (node (ref "X9") (pin "M2") (pinfunction "CGND2_M2") (pintype "bidirectional"))
      (node (ref "XB1") (pin "10") (pinfunction "GND_10") (pintype "power_in"))
      (node (ref "XB1") (pin "9") (pinfunction "~{DTR}/SLEEP_RQ/DI8_9") (pintype "bidirectional"))
    )
    (net (code "21") (name "HOME_SHUTTER_CLOSED") (class "Default")
      (node (ref "IC5") (pin "P$17") (pinfunction "B1_P$17") (pintype "bidirectional"))
      (node (ref "U$1") (pin "2") (pinfunction "2_2") (pintype "bidirectional"))
    )
    (net (code "22") (name "HOME_SHUTTER_CLOSED_5V") (class "Default")
      (node (ref "IC5") (pin "P$3") (pinfunction "A1_P$3") (pintype "bidirectional"))
      (node (ref "R18") (pin "2") (pinfunction "2_2") (pintype "passive"))
      (node (ref "X1") (pin "2") (pinfunction "KL_2") (pintype "passive"))
    )
    (net (code "23") (name "INT_N") (class "Default")
      (node (ref "U$1") (pin "32") (pinfunction "32_32") (pintype "bidirectional"))
      (node (ref "U1") (pin "36") (pinfunction "INT_N_36") (pintype "passive"))
    )
    (net (code "24") (name "LINK_ACK") (class "Default")
      (node (ref "U1") (pin "25") (pinfunction "LINKLED_25") (pintype "passive"))
      (node (ref "X9") (pin "10") (pinfunction "C-R_10") (pintype "passive"))
    )
    (net (code "25") (name "M_DIR") (class "Default")
      (node (ref "IC6") (pin "P$3") (pinfunction "A1_P$3") (pintype "bidirectional"))
      (node (ref "U$1") (pin "11") (pinfunction "11_11") (pintype "bidirectional"))
    )
    (net (code "26") (name "M_DIR_5V") (class "Default")
      (node (ref "IC6") (pin "P$17") (pinfunction "B1_P$17") (pintype "bidirectional"))
      (node (ref "R19") (pin "2") (pinfunction "2_2") (pintype "passive"))
      (node (ref "X6") (pin "3") (pinfunction "KL_3") (pintype "passive"))
    )
    (net (code "27") (name "M_EN") (class "Default")
      (node (ref "IC6") (pin "P$2") (pinfunction "A0_P$2") (pintype "bidirectional"))
      (node (ref "U$1") (pin "10") (pinfunction "10_10") (pintype "bidirectional"))
    )
    (net (code "28") (name "M_EN_5V") (class "Default")
      (node (ref "IC6") (pin "P$18") (pinfunction "B0_P$18") (pintype "bidirectional"))
      (node (ref "R14") (pin "2") (pinfunction "2_2") (pintype "passive"))
      (node (ref "X6") (pin "1") (pinfunction "KL_1") (pintype "passive"))
    )
    (net (code "29") (name "M_STEP") (class "Default")
      (node (ref "IC6") (pin "P$4") (pinfunction "A2_P$4") (pintype "bidirectional"))
      (node (ref "U$1") (pin "12") (pinfunction "12_12") (pintype "bidirectional"))
    )
    (net (code "30") (name "M_STEP_5V") (class "Default")
      (node (ref "IC6") (pin "P$16") (pinfunction "B2_P$16") (pintype "bidirectional"))
      (node (ref "R13") (pin "1") (pinfunction "1_1") (pintype "passive"))
      (node (ref "X6") (pin "5") (pinfunction "KL_5") (pintype "passive"))
    )
    (net (code "31") (name "Net-(IC3-3V3OUT)") (class "Default")
      (node (ref "C8") (pin "1") (pinfunction "1_1") (pintype "passive"))
      (node (ref "IC3") (pin "17") (pinfunction "3V3OUT_17") (pintype "output"))
    )
    (net (code "32") (name "Net-(IC3-~{CTS})") (class "Default")
      (node (ref "IC3") (pin "11") (pinfunction "~{CTS}_11") (pintype "input"))
      (node (ref "IC3") (pin "3") (pinfunction "~{RTS}_3") (pintype "output"))
    )
    (net (code "33") (name "Net-(IC3-~{DCD})") (class "Default")
      (node (ref "IC3") (pin "10") (pinfunction "~{DCD}_10") (pintype "input"))
      (node (ref "IC3") (pin "2") (pinfunction "~{DTR}_2") (pintype "output"))
      (node (ref "IC3") (pin "9") (pinfunction "~{DSR}_9") (pintype "input"))
    )
    (net (code "34") (name "Net-(R2-Pad2)") (class "Default")
      (node (ref "R2") (pin "2") (pinfunction "2_2") (pintype "passive"))
      (node (ref "R7") (pin "1") (pinfunction "1_1") (pintype "passive"))
    )
    (net (code "35") (name "Net-(R7-Pad2)") (class "Default")
      (node (ref "R7") (pin "2") (pinfunction "2_2") (pintype "passive"))
      (node (ref "R8") (pin "1") (pinfunction "1_1") (pintype "passive"))
    )
    (net (code "36") (name "Net-(R10-Pad1)") (class "Default")
      (node (ref "R10") (pin "1") (pinfunction "1_1") (pintype "passive"))
      (node (ref "R8") (pin "2") (pinfunction "2_2") (pintype "passive"))
    )
    (net (code "37") (name "Net-(R31-Pad1)") (class "Default")
      (node (ref "R31") (pin "1") (pinfunction "1_1") (pintype "passive"))
      (node (ref "U1") (pin "38") (pinfunction "RSVD_38") (pintype "passive"))
    )
    (net (code "38") (name "Net-(R32-Pad1)") (class "Default")
      (node (ref "R32") (pin "1") (pinfunction "1_1") (pintype "passive"))
      (node (ref "U1") (pin "39") (pinfunction "RSVD_39") (pintype "passive"))
    )
    (net (code "39") (name "Net-(R33-Pad1)") (class "Default")
      (node (ref "R33") (pin "1") (pinfunction "1_1") (pintype "passive"))
      (node (ref "U1") (pin "40") (pinfunction "RSVD_40") (pintype "passive"))
    )
    (net (code "40") (name "Net-(R34-Pad1)") (class "Default")
      (node (ref "R34") (pin "1") (pinfunction "1_1") (pintype "passive"))
      (node (ref "U1") (pin "41") (pinfunction "RSVD_41") (pintype "passive"))
    )
    (net (code "41") (name "Net-(R35-Pad1)") (class "Default")
      (node (ref "R35") (pin "1") (pinfunction "1_1") (pintype "passive"))
      (node (ref "U1") (pin "42") (pinfunction "RSVD_42") (pintype "passive"))
    )
    (net (code "42") (name "Net-(R40-Pad2)") (class "Default")
      (node (ref "R40") (pin "2") (pinfunction "2_2") (pintype "passive"))
      (node (ref "U1") (pin "23") (pinfunction "RSVD_23") (pintype "passive"))
    )
    (net (code "43") (name "Net-(U1-1V2O)") (class "Default")
      (node (ref "C18") (pin "2") (pinfunction "2_2") (pintype "passive"))
      (node (ref "U1") (pin "22") (pinfunction "1V2O_22") (pintype "passive"))
    )
    (net (code "44") (name "Net-(U1-EXRES1)") (class "Default")
      (node (ref "R39") (pin "1") (pinfunction "1_1") (pintype "passive"))
      (node (ref "U1") (pin "10") (pinfunction "EXRES1_10") (pintype "passive"))
    )
    (net (code "45") (name "Net-(U1-PMODE0)") (class "Default")
      (node (ref "R38") (pin "1") (pinfunction "1_1") (pintype "passive"))
      (node (ref "U1") (pin "45") (pinfunction "PMODE0_45") (pintype "passive"))
    )
    (net (code "46") (name "Net-(U1-PMODE1)") (class "Default")
      (node (ref "R37") (pin "1") (pinfunction "1_1") (pintype "passive"))
      (node (ref "U1") (pin "44") (pinfunction "PMODE1_44") (pintype "passive"))
    )
    (net (code "47") (name "Net-(U1-PMODE2)") (class "Default")
      (node (ref "R36") (pin "1") (pinfunction "1_1") (pintype "passive"))
      (node (ref "U1") (pin "43") (pinfunction "PMODE2_43") (pintype "passive"))
    )
    (net (code "48") (name "Net-(U1-TOCAP)") (class "Default")
      (node (ref "C19") (pin "2") (pinfunction "2_2") (pintype "passive"))
      (node (ref "U1") (pin "20") (pinfunction "TOCAP_20") (pintype "passive"))
    )
    (net (code "49") (name "Net-(X9-A-R)") (class "Default")
      (node (ref "R29") (pin "1") (pinfunction "1_1") (pintype "passive"))
      (node (ref "X9") (pin "9") (pinfunction "A-R_9") (pintype "passive"))
    )
    (net (code "50") (name "Net-(X9-AL)") (class "Default")
      (node (ref "R28") (pin "1") (pinfunction "1_1") (pintype "passive"))
      (node (ref "X9") (pin "12") (pinfunction "AL_12") (pintype "passive"))
    )
    (net (code "51") (name "Net-(X9-CR)") (class "Default")
      (node (ref "C22") (pin "1") (pinfunction "1_1") (pintype "passive"))
      (node (ref "R26") (pin "2") (pinfunction "2_2") (pintype "passive"))
      (node (ref "R27") (pin "2") (pinfunction "2_2") (pintype "passive"))
      (node (ref "X9") (pin "6") (pinfunction "CR_6") (pintype "input"))
    )
    (net (code "52") (name "Net-(X9-CT)") (class "Default")
      (node (ref "C10") (pin "1") (pinfunction "1_1") (pintype "passive"))
      (node (ref "R23") (pin "1") (pinfunction "1_1") (pintype "passive"))
      (node (ref "X9") (pin "3") (pinfunction "CT_3") (pintype "input"))
    )
    (net (code "53") (name "Net-(X9-RD+)") (class "Default")
      (node (ref "C15") (pin "2") (pinfunction "2_2") (pintype "passive"))
      (node (ref "X9") (pin "7") (pinfunction "RD+_7") (pintype "input"))
    )
    (net (code "54") (name "Net-(X9-RD-)") (class "Default")
      (node (ref "C21") (pin "2") (pinfunction "2_2") (pintype "passive"))
      (node (ref "X9") (pin "8") (pinfunction "RD-_8") (pintype "input"))
    )
    (net (code "55") (name "Net-(XB1-~{CTS}{slash}DIO7)") (class "Default")
      (node (ref "XB1") (pin "12") (pinfunction "~{CTS}/DIO7_12") (pintype "bidirectional"))
      (node (ref "XB1") (pin "16") (pinfunction "~{RTS}/AD6/DIO6_16") (pintype "bidirectional"))
    )
    (net (code "56") (name "RESET") (class "Default")
      (node (ref "U$1") (pin "RESET") (pinfunction "RESET_RESET") (pintype "bidirectional"))
      (node (ref "U$2") (pin "1") (pinfunction "~{RST}_1") (pintype "bidirectional"))
    )
    (net (code "57") (name "RG-11") (class "Default")
      (node (ref "IC5") (pin "P$13") (pinfunction "B5_P$13") (pintype "bidirectional"))
      (node (ref "U$1") (pin "7") (pinfunction "7_7") (pintype "bidirectional"))
    )
    (net (code "58") (name "RG-11-IN_5V") (class "Default")
      (node (ref "C1") (pin "1") (pinfunction "1_1") (pintype "passive"))
      (node (ref "IC5") (pin "P$7") (pinfunction "A5_P$7") (pintype "bidirectional"))
      (node (ref "R4") (pin "1") (pinfunction "1_1") (pintype "passive"))
      (node (ref "R5") (pin "1") (pinfunction "1_1") (pintype "passive"))
    )
    (net (code "59") (name "RG-11-IN_EXT") (class "Default")
      (node (ref "R5") (pin "2") (pinfunction "2_2") (pintype "passive"))
      (node (ref "X5") (pin "2") (pinfunction "KL_2") (pintype "passive"))
    )
    (net (code "60") (name "RX2") (class "Default")
      (node (ref "IC3") (pin "1") (pinfunction "TXD_1") (pintype "output"))
      (node (ref "U$1") (pin "17") (pinfunction "17(RX2)_17") (pintype "bidirectional"))
    )
    (net (code "61") (name "RXN") (class "Default")
      (node (ref "C21") (pin "1") (pinfunction "1_1") (pintype "passive"))
      (node (ref "R26") (pin "1") (pinfunction "1_1") (pintype "passive"))
      (node (ref "U1") (pin "5") (pinfunction "RXN_5") (pintype "passive"))
    )
    (net (code "62") (name "RXP") (class "Default")
      (node (ref "C15") (pin "1") (pinfunction "1_1") (pintype "passive"))
      (node (ref "R27") (pin "1") (pinfunction "1_1") (pintype "passive"))
      (node (ref "U1") (pin "6") (pinfunction "RXP_6") (pintype "passive"))
    )
    (net (code "63") (name "SCL") (class "Default")
      (node (ref "IC1") (pin "6") (pinfunction "SCL_6") (pintype "input"))
      (node (ref "R3") (pin "1") (pinfunction "1_1") (pintype "passive"))
      (node (ref "U$1") (pin "SCL1") (pinfunction "SCL1_SCL1") (pintype "bidirectional"))
    )
    (net (code "64") (name "SCLK") (class "Default")
      (node (ref "U$1") (pin "SCK") (pinfunction "SCK_SCK") (pintype "bidirectional"))
      (node (ref "U1") (pin "33") (pinfunction "SCLK_33") (pintype "passive"))
    )
    (net (code "65") (name "SDA") (class "Default")
      (node (ref "IC1") (pin "5") (pinfunction "SDA_5") (pintype "bidirectional"))
      (node (ref "R1") (pin "1") (pinfunction "1_1") (pintype "passive"))
      (node (ref "U$1") (pin "SDA1") (pinfunction "SDA1_SDA1") (pintype "bidirectional"))
    )
    (net (code "66") (name "SDI") (class "Default")
      (node (ref "U$1") (pin "MISO") (pinfunction "SDI_MISO") (pintype "bidirectional"))
      (node (ref "U1") (pin "34") (pinfunction "MISO_34") (pintype "passive"))
    )
    (net (code "67") (name "SDO") (class "Default")
      (node (ref "U$1") (pin "MOSI") (pinfunction "SDO_MOSI") (pintype "bidirectional"))
      (node (ref "U1") (pin "35") (pinfunction "MOSI_35") (pintype "passive"))
    )
    (net (code "68") (name "SHUTTER_OPENED") (class "Default")
      (node (ref "IC5") (pin "P$12") (pinfunction "B6_P$12") (pintype "bidirectional"))
      (node (ref "U$1") (pin "3") (pinfunction "3_3") (pintype "bidirectional"))
    )
    (net (code "69") (name "SHUTTER_OPENED_5V") (class "Default")
      (node (ref "IC5") (pin "P$8") (pinfunction "A6_P$8") (pintype "bidirectional"))
      (node (ref "R17") (pin "2") (pinfunction "2_2") (pintype "passive"))
      (node (ref "X3") (pin "2") (pinfunction "KL_2") (pintype "passive"))
    )
    (net (code "70") (name "TX2") (class "Default")
      (node (ref "IC3") (pin "5") (pinfunction "RXD_5") (pintype "input"))
      (node (ref "U$1") (pin "16") (pinfunction "16(TX2)_16") (pintype "bidirectional"))
    )
    (net (code "71") (name "TXN") (class "Default")
      (node (ref "R25") (pin "1") (pinfunction "1_1") (pintype "passive"))
      (node (ref "U1") (pin "1") (pinfunction "TXN_1") (pintype "passive"))
      (node (ref "X9") (pin "2") (pinfunction "TD-_2") (pintype "input"))
    )
    (net (code "72") (name "TXP") (class "Default")
      (node (ref "R24") (pin "1") (pinfunction "1_1") (pintype "passive"))
      (node (ref "U1") (pin "2") (pinfunction "TXP_2") (pintype "passive"))
      (node (ref "X9") (pin "1") (pinfunction "TD+_1") (pintype "input"))
    )
    (net (code "73") (name "USBDM") (class "Default")
      (node (ref "IC3") (pin "16") (pinfunction "USBDM_16") (pintype "bidirectional"))
      (node (ref "X13") (pin "2") (pinfunction "2_2") (pintype "passive"))
    )
    (net (code "74") (name "USBDP") (class "Default")
      (node (ref "IC3") (pin "15") (pinfunction "USBDP_15") (pintype "bidirectional"))
      (node (ref "X13") (pin "3") (pinfunction "3_3") (pintype "passive"))
    )
    (net (code "75") (name "USB_VCC") (class "Default")
      (node (ref "X13") (pin "1") (pinfunction "1_1") (pintype "passive"))
    )
    (net (code "76") (name "VCC") (class "Default")
      (node (ref "C6") (pin "1") (pinfunction "1_1") (pintype "passive"))
      (node (ref "C7") (pin "1") (pinfunction "1_1") (pintype "passive"))
      (node (ref "IC3") (pin "20") (pinfunction "VCC_20") (pintype "power_in"))
      (node (ref "IC6") (pin "P$1") (pinfunction "DIR_P$1") (pintype "input"))
      (node (ref "IC6") (pin "P$20") (pinfunction "VDD_P$20") (pintype "power_in"))
      (node (ref "R12") (pin "2") (pinfunction "2_2") (pintype "passive"))
      (node (ref "R13") (pin "2") (pinfunction "2_2") (pintype "passive"))
      (node (ref "R14") (pin "1") (pinfunction "1_1") (pintype "passive"))
      (node (ref "R15") (pin "1") (pinfunction "1_1") (pintype "passive"))
      (node (ref "R16") (pin "1") (pinfunction "1_1") (pintype "passive"))
      (node (ref "R17") (pin "1") (pinfunction "1_1") (pintype "passive"))
      (node (ref "R18") (pin "1") (pinfunction "1_1") (pintype "passive"))
      (node (ref "R19") (pin "1") (pinfunction "1_1") (pintype "passive"))
      (node (ref "R20") (pin "2") (pinfunction "2_2") (pintype "passive"))
      (node (ref "R21") (pin "1") (pinfunction "1_1") (pintype "passive"))
      (node (ref "R4") (pin "2") (pinfunction "2_2") (pintype "passive"))
      (node (ref "U$1") (pin "+5V@1") (pinfunction "+5V_+5V@1") (pintype "power_in"))
      (node (ref "U$1") (pin "+5V@3") (pinfunction "+5V_+5V@3") (pintype "power_in"))
      (node (ref "U$1") (pin "+5V@4") (pinfunction "+5V_+5V@4") (pintype "power_in"))
      (node (ref "X6") (pin "2") (pinfunction "KL_2") (pintype "passive"))
      (node (ref "X6") (pin "4") (pinfunction "KL_4") (pintype "passive"))
      (node (ref "X6") (pin "6") (pinfunction "KL_6") (pintype "passive"))
    )
    (net (code "77") (name "VPIN") (class "Default")
      (node (ref "R2") (pin "1") (pinfunction "1_1") (pintype "passive"))
      (node (ref "R6") (pin "2") (pinfunction "2_2") (pintype "passive"))
      (node (ref "U$1") (pin "A0") (pinfunction "A0_A0") (pintype "bidirectional"))
    )
    (net (code "78") (name "XBEE_DIN") (class "Default")
      (node (ref "U$1") (pin "18") (pinfunction "18(TX1)_18") (pintype "bidirectional"))
      (node (ref "XB1") (pin "3") (pinfunction "DIN/~{CONFIG}_3") (pintype "input"))
    )
    (net (code "79") (name "XBEE_DOUT") (class "Default")
      (node (ref "U$1") (pin "19") (pinfunction "19(RX1)_19") (pintype "bidirectional"))
      (node (ref "XB1") (pin "2") (pinfunction "DOUT_2") (pintype "output"))
    )
    (net (code "80") (name "XBEE_RESET") (class "Default")
      (node (ref "U$1") (pin "8") (pinfunction "8_8") (pintype "bidirectional"))
      (node (ref "XB1") (pin "5") (pinfunction "~{RESET}_5") (pintype "input"))
    )
    (net (code "81") (name "XI") (class "Default")
      (node (ref "25MHZ") (pin "3") (pinfunction "FO_3") (pintype "output"))
      (node (ref "U1") (pin "30") (pinfunction "XI/CLKIN_30") (pintype "passive"))
    )
    (net (code "82") (name "XO") (class "Default")
      (node (ref "U1") (pin "31") (pinfunction "XO_31") (pintype "passive"))
    )
    (net (code "83") (name "unconnected-(IC1-WP-Pad7)") (class "Default")
      (node (ref "IC1") (pin "7") (pinfunction "WP_7") (pintype "input"))
    )
    (net (code "84") (name "unconnected-(IC3-CBUS0-Pad23)") (class "Default")
      (node (ref "IC3") (pin "23") (pinfunction "CBUS0_23") (pintype "bidirectional"))
    )
    (net (code "85") (name "unconnected-(IC3-CBUS1-Pad22)") (class "Default")
      (node (ref "IC3") (pin "22") (pinfunction "CBUS1_22") (pintype "bidirectional"))
    )
    (net (code "86") (name "unconnected-(IC3-CBUS2-Pad13)") (class "Default")
      (node (ref "IC3") (pin "13") (pinfunction "CBUS2_13") (pintype "bidirectional"))
    )
    (net (code "87") (name "unconnected-(IC3-CBUS3-Pad14)") (class "Default")
      (node (ref "IC3") (pin "14") (pinfunction "CBUS3_14") (pintype "bidirectional"))
    )
    (net (code "88") (name "unconnected-(IC3-CBUS4-Pad12)") (class "Default")
      (node (ref "IC3") (pin "12") (pinfunction "CBUS4_12") (pintype "bidirectional"))
    )
    (net (code "89") (name "unconnected-(IC3-OSCI-Pad27)") (class "Default")
      (node (ref "IC3") (pin "27") (pinfunction "OSCI_27") (pintype "input"))
    )
    (net (code "90") (name "unconnected-(IC3-OSCO-Pad28)") (class "Default")
      (node (ref "IC3") (pin "28") (pinfunction "OSCO_28") (pintype "output"))
    )
    (net (code "91") (name "unconnected-(IC3-TEST-Pad26)") (class "Default")
      (node (ref "IC3") (pin "26") (pinfunction "TEST_26") (pintype "input"))
    )
    (net (code "92") (name "unconnected-(IC3-~{RI}-Pad6)") (class "Default")
      (node (ref "IC3") (pin "6") (pinfunction "~{RI}_6") (pintype "input"))
    )
    (net (code "93") (name "unconnected-(IC5A-B4-PadP$14)") (class "Default")
      (node (ref "IC5") (pin "P$14") (pinfunction "B4_P$14") (pintype "bidirectional"))
    )
    (net (code "94") (name "unconnected-(IC6A-B4-PadP$14)") (class "Default")
      (node (ref "IC6") (pin "P$14") (pinfunction "B4_P$14") (pintype "bidirectional"))
    )
    (net (code "95") (name "unconnected-(IC6A-B5-PadP$13)") (class "Default")
      (node (ref "IC6") (pin "P$13") (pinfunction "B5_P$13") (pintype "bidirectional"))
    )
    (net (code "96") (name "unconnected-(IC6A-B6-PadP$12)") (class "Default")
      (node (ref "IC6") (pin "P$12") (pinfunction "B6_P$12") (pintype "bidirectional"))
    )
    (net (code "97") (name "unconnected-(IC6A-B7-PadP$11)") (class "Default")
      (node (ref "IC6") (pin "P$11") (pinfunction "B7_P$11") (pintype "bidirectional"))
    )
    (net (code "98") (name "unconnected-(U$1-(N{slash}C)-PadN{slash}C)") (class "Default")
      (node (ref "U$1") (pin "N/C") (pinfunction "(N/C)_N/C") (pintype "no_connect"))
    )
    (net (code "99") (name "unconnected-(U$1-0(RX)-Pad0)") (class "Default")
      (node (ref "U$1") (pin "0") (pinfunction "0(RX)_0") (pintype "bidirectional"))
    )
    (net (code "100") (name "unconnected-(U$1-1(TX)-Pad1)") (class "Default")
      (node (ref "U$1") (pin "1") (pinfunction "1(TX)_1") (pintype "bidirectional"))
    )
    (net (code "101") (name "unconnected-(U$1-14(TX3)-Pad14)") (class "Default")
      (node (ref "U$1") (pin "14") (pinfunction "14(TX3)_14") (pintype "bidirectional"))
    )
    (net (code "102") (name "unconnected-(U$1-15(RX3)-Pad15)") (class "Default")
      (node (ref "U$1") (pin "15") (pinfunction "15(RX3)_15") (pintype "bidirectional"))
    )
    (net (code "103") (name "unconnected-(U$1-20(SDA)-Pad20)") (class "Default")
      (node (ref "U$1") (pin "20") (pinfunction "20(SDA)_20") (pintype "bidirectional"))
    )
    (net (code "104") (name "unconnected-(U$1-21(SCL)-Pad21)") (class "Default")
      (node (ref "U$1") (pin "21") (pinfunction "21(SCL)_21") (pintype "bidirectional"))
    )
    (net (code "105") (name "unconnected-(U$1-CANRX-PadA14)") (class "Default")
      (node (ref "U$1") (pin "A14") (pinfunction "CANRX_A14") (pintype "bidirectional"))
    )
    (net (code "106") (name "unconnected-(U$1-CANTX-PadA15)") (class "Default")
      (node (ref "U$1") (pin "A15") (pinfunction "CANTX_A15") (pintype "bidirectional"))
    )
    (net (code "107") (name "unconnected-(U$1-DAC0-PadA12)") (class "Default")
      (node (ref "U$1") (pin "A12") (pinfunction "DAC0_A12") (pintype "bidirectional"))
    )
    (net (code "108") (name "unconnected-(U$1-DAC1-PadA13)") (class "Default")
      (node (ref "U$1") (pin "A13") (pinfunction "DAC1_A13") (pintype "bidirectional"))
    )
    (net (code "109") (name "unconnected-(U$1-IOREF-PadI{slash}OREF)") (class "Default")
      (node (ref "U$1") (pin "I/OREF") (pinfunction "IOREF_I/OREF") (pintype "bidirectional"))
    )
    (net (code "110") (name "unconnected-(U$1-Pad4)") (class "Default")
      (node (ref "U$1") (pin "4") (pinfunction "4_4") (pintype "bidirectional"))
    )
    (net (code "111") (name "unconnected-(U$1-Pad9)") (class "Default")
      (node (ref "U$1") (pin "9") (pinfunction "9_9") (pintype "bidirectional"))
    )
    (net (code "112") (name "unconnected-(U$1-Pad22)") (class "Default")
      (node (ref "U$1") (pin "22") (pinfunction "22_22") (pintype "bidirectional"))
    )
    (net (code "113") (name "unconnected-(U$1-Pad24)") (class "Default")
      (node (ref "U$1") (pin "24") (pinfunction "24_24") (pintype "bidirectional"))
    )
    (net (code "114") (name "unconnected-(U$1-Pad25)") (class "Default")
      (node (ref "U$1") (pin "25") (pinfunction "25_25") (pintype "bidirectional"))
    )
    (net (code "115") (name "unconnected-(U$1-Pad26)") (class "Default")
      (node (ref "U$1") (pin "26") (pinfunction "26_26") (pintype "bidirectional"))
    )
    (net (code "116") (name "unconnected-(U$1-Pad27)") (class "Default")
      (node (ref "U$1") (pin "27") (pinfunction "27_27") (pintype "bidirectional"))
    )
    (net (code "117") (name "unconnected-(U$1-Pad28)") (class "Default")
      (node (ref "U$1") (pin "28") (pinfunction "28_28") (pintype "bidirectional"))
    )
    (net (code "118") (name "unconnected-(U$1-Pad29)") (class "Default")
      (node (ref "U$1") (pin "29") (pinfunction "29_29") (pintype "bidirectional"))
    )
    (net (code "119") (name "unconnected-(U$1-Pad30)") (class "Default")
      (node (ref "U$1") (pin "30") (pinfunction "30_30") (pintype "bidirectional"))
    )
    (net (code "120") (name "unconnected-(U$1-Pad31)") (class "Default")
      (node (ref "U$1") (pin "31") (pinfunction "31_31") (pintype "bidirectional"))
    )
    (net (code "121") (name "unconnected-(U$1-Pad33)") (class "Default")
      (node (ref "U$1") (pin "33") (pinfunction "33_33") (pintype "bidirectional"))
    )
    (net (code "122") (name "unconnected-(U$1-Pad34)") (class "Default")
      (node (ref "U$1") (pin "34") (pinfunction "34_34") (pintype "bidirectional"))
    )
    (net (code "123") (name "unconnected-(U$1-Pad35)") (class "Default")
      (node (ref "U$1") (pin "35") (pinfunction "35_35") (pintype "bidirectional"))
    )
    (net (code "124") (name "unconnected-(U$1-Pad36)") (class "Default")
      (node (ref "U$1") (pin "36") (pinfunction "36_36") (pintype "bidirectional"))
    )
    (net (code "125") (name "unconnected-(U$1-Pad37)") (class "Default")
      (node (ref "U$1") (pin "37") (pinfunction "37_37") (pintype "bidirectional"))
    )
    (net (code "126") (name "unconnected-(U$1-Pad38)") (class "Default")
      (node (ref "U$1") (pin "38") (pinfunction "38_38") (pintype "bidirectional"))
    )
    (net (code "127") (name "unconnected-(U$1-Pad39)") (class "Default")
      (node (ref "U$1") (pin "39") (pinfunction "39_39") (pintype "bidirectional"))
    )
    (net (code "128") (name "unconnected-(U$1-Pad40)") (class "Default")
      (node (ref "U$1") (pin "40") (pinfunction "40_40") (pintype "bidirectional"))
    )
    (net (code "129") (name "unconnected-(U$1-Pad41)") (class "Default")
      (node (ref "U$1") (pin "41") (pinfunction "41_41") (pintype "bidirectional"))
    )
    (net (code "130") (name "unconnected-(U$1-Pad42)") (class "Default")
      (node (ref "U$1") (pin "42") (pinfunction "42_42") (pintype "bidirectional"))
    )
    (net (code "131") (name "unconnected-(U$1-Pad43)") (class "Default")
      (node (ref "U$1") (pin "43") (pinfunction "43_43") (pintype "bidirectional"))
    )
    (net (code "132") (name "unconnected-(U$1-Pad44)") (class "Default")
      (node (ref "U$1") (pin "44") (pinfunction "44_44") (pintype "bidirectional"))
    )
    (net (code "133") (name "unconnected-(U$1-Pad45)") (class "Default")
      (node (ref "U$1") (pin "45") (pinfunction "45_45") (pintype "bidirectional"))
    )
    (net (code "134") (name "unconnected-(U$1-Pad46)") (class "Default")
      (node (ref "U$1") (pin "46") (pinfunction "46_46") (pintype "bidirectional"))
    )
    (net (code "135") (name "unconnected-(U$1-Pad47)") (class "Default")
      (node (ref "U$1") (pin "47") (pinfunction "47_47") (pintype "bidirectional"))
    )
    (net (code "136") (name "unconnected-(U$1-Pad48)") (class "Default")
      (node (ref "U$1") (pin "48") (pinfunction "48_48") (pintype "bidirectional"))
    )
    (net (code "137") (name "unconnected-(U$1-Pad49)") (class "Default")
      (node (ref "U$1") (pin "49") (pinfunction "49_49") (pintype "bidirectional"))
    )
    (net (code "138") (name "unconnected-(U$1-Pad50)") (class "Default")
      (node (ref "U$1") (pin "50") (pinfunction "50_50") (pintype "bidirectional"))
    )
    (net (code "139") (name "unconnected-(U$1-Pad51)") (class "Default")
      (node (ref "U$1") (pin "51") (pinfunction "51_51") (pintype "bidirectional"))
    )
    (net (code "140") (name "unconnected-(U$1-PadA1)") (class "Default")
      (node (ref "U$1") (pin "A1") (pinfunction "A1_A1") (pintype "bidirectional"))
    )
    (net (code "141") (name "unconnected-(U$1-PadA2)") (class "Default")
      (node (ref "U$1") (pin "A2") (pinfunction "A2_A2") (pintype "bidirectional"))
    )
    (net (code "142") (name "unconnected-(U$1-PadA3)") (class "Default")
      (node (ref "U$1") (pin "A3") (pinfunction "A3_A3") (pintype "bidirectional"))
    )
    (net (code "143") (name "unconnected-(U$1-PadA6)") (class "Default")
      (node (ref "U$1") (pin "A6") (pinfunction "A6_A6") (pintype "bidirectional"))
    )
    (net (code "144") (name "unconnected-(U$1-PadA7)") (class "Default")
      (node (ref "U$1") (pin "A7") (pinfunction "A7_A7") (pintype "bidirectional"))
    )
    (net (code "145") (name "unconnected-(U$1-PadA8)") (class "Default")
      (node (ref "U$1") (pin "A8") (pinfunction "A8_A8") (pintype "bidirectional"))
    )
    (net (code "146") (name "unconnected-(U$1-PadA9)") (class "Default")
      (node (ref "U$1") (pin "A9") (pinfunction "A9_A9") (pintype "bidirectional"))
    )
    (net (code "147") (name "unconnected-(U$1-PadA10)") (class "Default")
      (node (ref "U$1") (pin "A10") (pinfunction "A10_A10") (pintype "bidirectional"))
    )
    (net (code "148") (name "unconnected-(U$1-PadA11)") (class "Default")
      (node (ref "U$1") (pin "A11") (pinfunction "A11_A11") (pintype "bidirectional"))
    )
    (net (code "149") (name "unconnected-(U$1-PadAREF)") (class "Default")
      (node (ref "U$1") (pin "AREF") (pinfunction "AREF_AREF") (pintype "bidirectional"))
    )
    (net (code "150") (name "unconnected-(U$1-PadRESET.)") (class "Default")
      (node (ref "U$1") (pin "RESET.") (pinfunction "RESET._RESET.") (pintype "bidirectional"))
    )
    (net (code "151") (name "unconnected-(U1-DNC-Pad7)") (class "Default")
      (node (ref "U1") (pin "7") (pinfunction "DNC_7") (pintype "passive"))
    )
    (net (code "152") (name "unconnected-(U1-DUPLED-Pad26)") (class "Default")
      (node (ref "U1") (pin "26") (pinfunction "DUPLED_26") (pintype "passive"))
    )
    (net (code "153") (name "unconnected-(U1-NC-Pad12)") (class "Default")
      (node (ref "U1") (pin "12") (pinfunction "NC_12") (pintype "passive"))
    )
    (net (code "154") (name "unconnected-(U1-NC-Pad13)") (class "Default")
      (node (ref "U1") (pin "13") (pinfunction "NC_13") (pintype "passive"))
    )
    (net (code "155") (name "unconnected-(U1-NC-Pad46)") (class "Default")
      (node (ref "U1") (pin "46") (pinfunction "NC_46") (pintype "passive"))
    )
    (net (code "156") (name "unconnected-(U1-NC-Pad47)") (class "Default")
      (node (ref "U1") (pin "47") (pinfunction "NC_47") (pintype "passive"))
    )
    (net (code "157") (name "unconnected-(U1-SPDLED-Pad24)") (class "Default")
      (node (ref "U1") (pin "24") (pinfunction "SPDLED_24") (pintype "passive"))
    )
    (net (code "158") (name "unconnected-(U1-VBG-Pad18)") (class "Default")
      (node (ref "U1") (pin "18") (pinfunction "VBG_18") (pintype "passive"))
    )
    (net (code "159") (name "unconnected-(XB1-AD0{slash}DIO0-Pad20)") (class "Default")
      (node (ref "XB1") (pin "20") (pinfunction "AD0/DIO0_20") (pintype "bidirectional"))
    )
    (net (code "160") (name "unconnected-(XB1-AD1{slash}DIO1-Pad19)") (class "Default")
      (node (ref "XB1") (pin "19") (pinfunction "AD1/DIO1_19") (pintype "bidirectional"))
    )
    (net (code "161") (name "unconnected-(XB1-AD2{slash}DIO2-Pad18)") (class "Default")
      (node (ref "XB1") (pin "18") (pinfunction "AD2/DIO2_18") (pintype "bidirectional"))
    )
    (net (code "162") (name "unconnected-(XB1-ASSOC{slash}AD5{slash}DIO5-Pad15)") (class "Default")
      (node (ref "XB1") (pin "15") (pinfunction "ASSOC/AD5/DIO5_15") (pintype "bidirectional"))
    )
    (net (code "163") (name "unconnected-(XB1-CD{slash}DOUT_EN{slash}DO8-Pad4)") (class "Default")
      (node (ref "XB1") (pin "4") (pinfunction "CD/DOUT_EN/DO8_4") (pintype "output"))
    )
    (net (code "164") (name "unconnected-(XB1-COORD_SEL{slash}AD3{slash}DIO3-Pad17)") (class "Default")
      (node (ref "XB1") (pin "17") (pinfunction "COORD_SEL/AD3/DIO3_17") (pintype "bidirectional"))
    )
    (net (code "165") (name "unconnected-(XB1-ON{slash}~{SLEEP}-Pad13)") (class "Default")
      (node (ref "XB1") (pin "13") (pinfunction "ON/~{SLEEP}_13") (pintype "output"))
    )
    (net (code "166") (name "unconnected-(XB1-PWM0{slash}RSSI-Pad6)") (class "Default")
      (node (ref "XB1") (pin "6") (pinfunction "PWM0/RSSI_6") (pintype "output"))
    )
    (net (code "167") (name "unconnected-(XB1-RF_TX{slash}AD4{slash}DIO4-Pad11)") (class "Default")
      (node (ref "XB1") (pin "11") (pinfunction "RF_TX/AD4/DIO4_11") (pintype "bidirectional"))
    )
    (net (code "168") (name "unconnected-(XB1-VREF-Pad14)") (class "Default")
      (node (ref "XB1") (pin "14") (pinfunction "VREF_14") (pintype "input"))
    )
  )
)
